# 1VD_1_5VD_1_8VD_3_3VD_3_3VA.net
KiCad netlist of a schematic drawn in Altium Designer
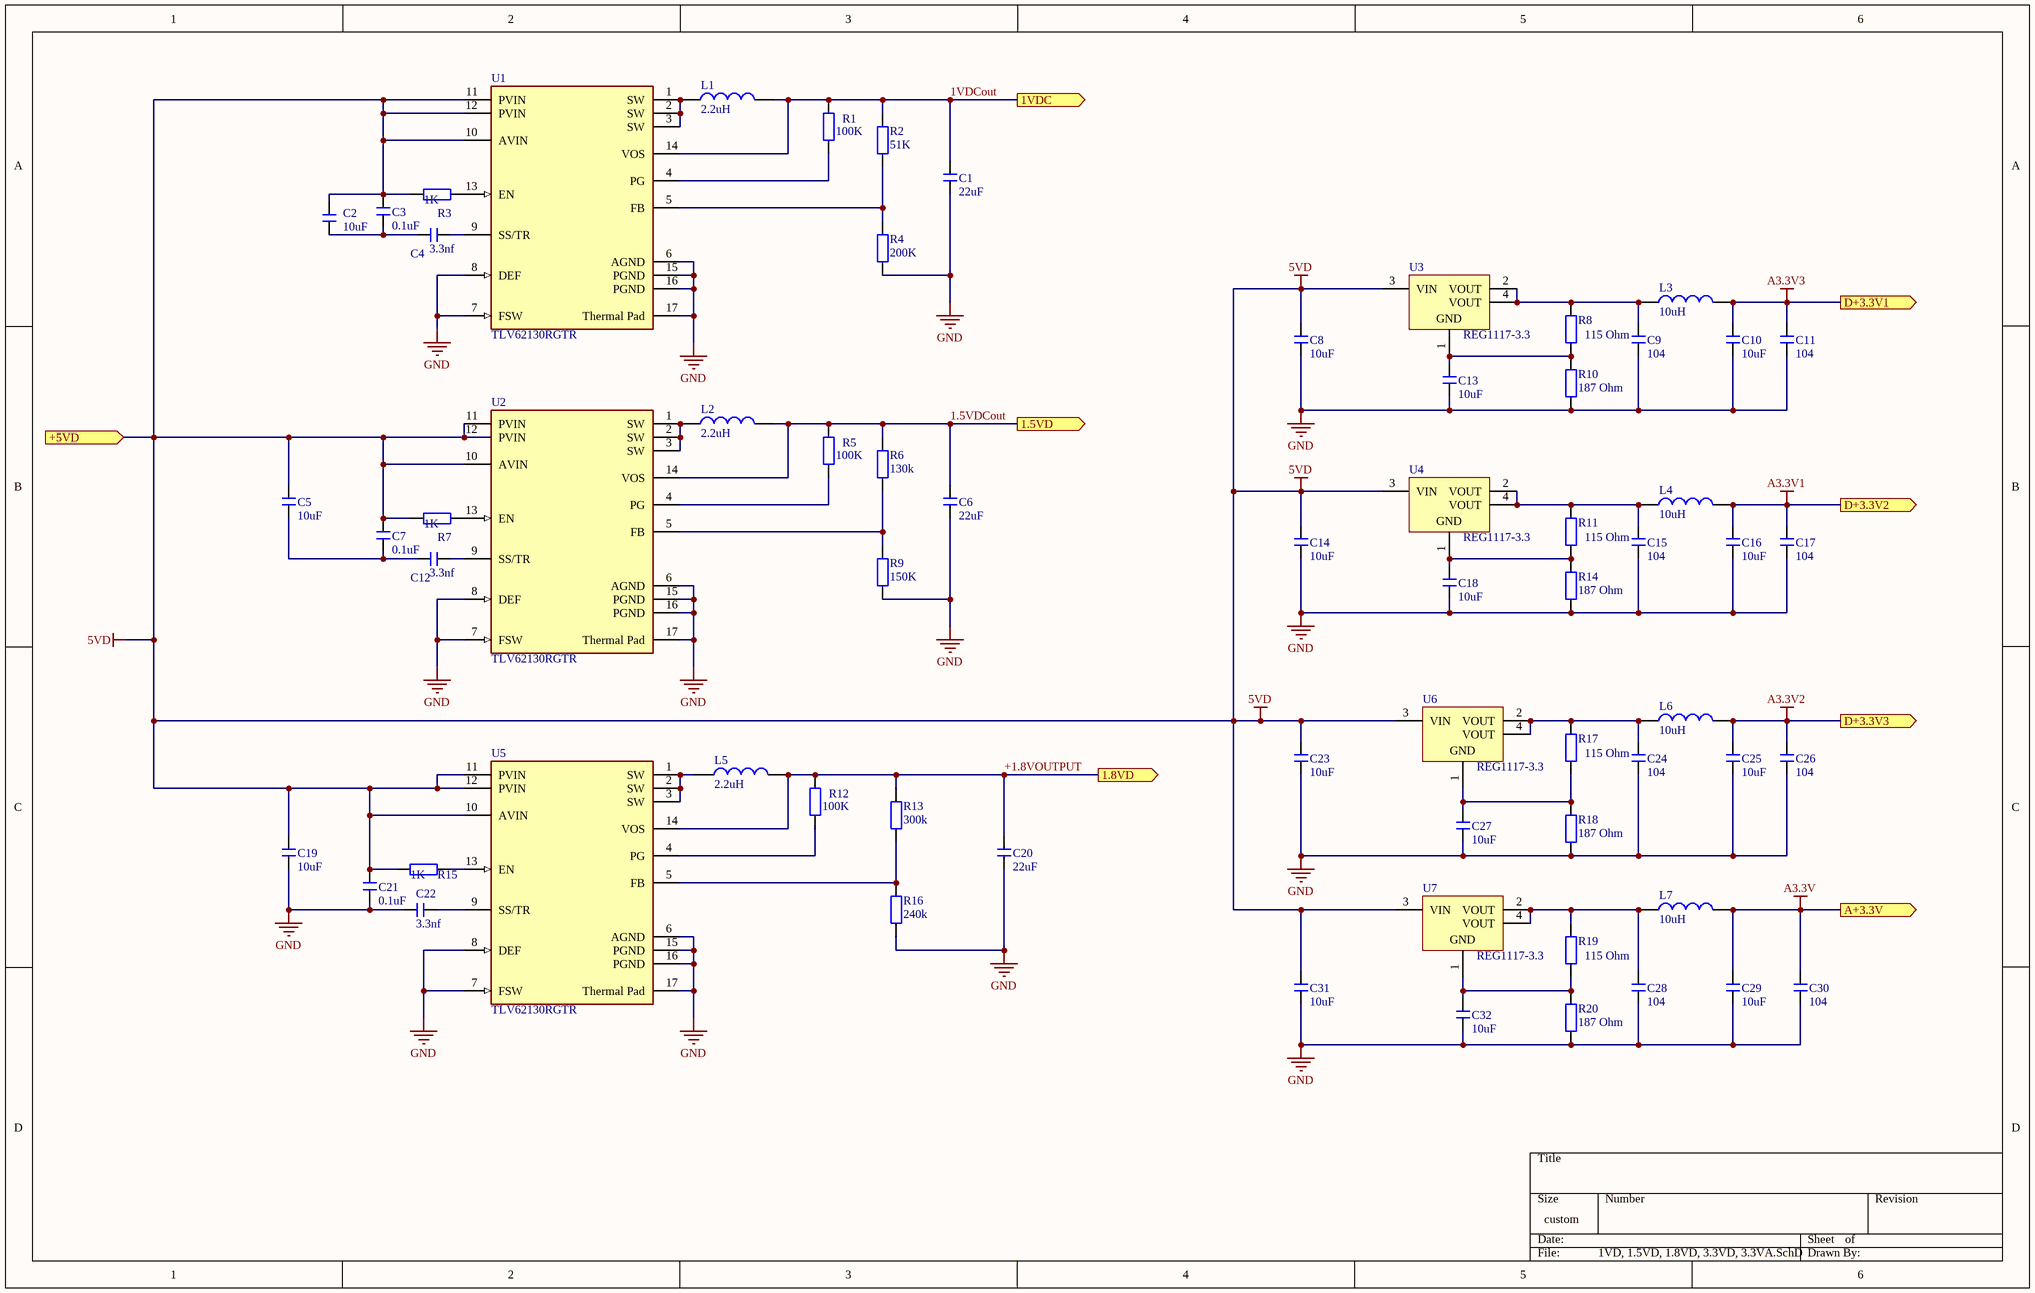
[diagram p0: 1VD, 1.5VD, 1.8VD, 3.3VD, 3.3VA.SchDoc]

(export (version "E")
  (design (tool "Eeschema 10.0.6"))
  (components
    (comp (ref "C1")
      (value "22uF")
      (footprint "C 0805_L")
      (description "贴片电容 22 µF, 6.3 V, Ceramic, 0805 Standard")
      (libsource (lib "0.1 - 电阻-电容-电感") (part "C"))
    )
    (comp (ref "C2")
      (value "10uF")
      (footprint "C 0805_L")
      (description "贴片电容 10 µF, 25 V, Ceramic, 1210 Standard")
      (libsource (lib "0.1 - 电阻-电容-电感") (part "C"))
    )
    (comp (ref "C3")
      (value "0.1uF")
      (footprint "C 0805_L")
      (description "贴片电容  \r\nC7 0.1 µF, 25V, Ceramic, 0603")
      (libsource (lib "0.1 - 电阻-电容-电感") (part "C"))
    )
    (comp (ref "C4")
      (value "3.3nf")
      (footprint "C 0805_L")
      (description "贴片电容 3300 pF, 25 V, Ceramic, 0603")
      (libsource (lib "0.1 - 电阻-电容-电感") (part "C"))
    )
    (comp (ref "C5")
      (value "10uF")
      (footprint "C 0805_L")
      (description "贴片电容 10 µF, 25 V, Ceramic, 1210 Standard")
      (libsource (lib "0.1 - 电阻-电容-电感") (part "C"))
    )
    (comp (ref "C6")
      (value "22uF")
      (footprint "C 0805_L")
      (description "贴片电容 22 µF, 6.3 V, Ceramic, 0805 Standard")
      (libsource (lib "0.1 - 电阻-电容-电感") (part "C"))
    )
    (comp (ref "C7")
      (value "0.1uF")
      (footprint "C 0805_L")
      (description "贴片电容 0.1 µF, 25V, Ceramic, 0603")
      (libsource (lib "0.1 - 电阻-电容-电感") (part "C"))
    )
    (comp (ref "C8")
      (value "10uF")
      (footprint "C 0805_L")
      (description "贴片电容")
      (libsource (lib "0.1 - 电阻-电容-电感") (part "C"))
    )
    (comp (ref "C9")
      (value "104")
      (footprint "C 0805_L")
      (description "贴片电容")
      (libsource (lib "0.1 - 电阻-电容-电感") (part "C"))
    )
    (comp (ref "C10")
      (value "10uF")
      (footprint "C 0805_L")
      (description "贴片电容")
      (libsource (lib "0.1 - 电阻-电容-电感") (part "C"))
    )
    (comp (ref "C11")
      (value "104")
      (footprint "C 0805_L")
      (description "贴片电容")
      (libsource (lib "0.1 - 电阻-电容-电感") (part "C"))
    )
    (comp (ref "C12")
      (value "3.3nf")
      (footprint "C 0805_L")
      (description "贴片电容 3300 pF, 25 V, Ceramic, 0603")
      (libsource (lib "0.1 - 电阻-电容-电感") (part "C"))
    )
    (comp (ref "C13")
      (value "10uF")
      (footprint "C 0805_L")
      (description "贴片电容")
      (libsource (lib "0.1 - 电阻-电容-电感") (part "C"))
    )
    (comp (ref "C14")
      (value "10uF")
      (footprint "C 0805_L")
      (description "贴片电容")
      (libsource (lib "0.1 - 电阻-电容-电感") (part "C"))
    )
    (comp (ref "C15")
      (value "104")
      (footprint "C 0805_L")
      (description "贴片电容")
      (libsource (lib "0.1 - 电阻-电容-电感") (part "C"))
    )
    (comp (ref "C16")
      (value "10uF")
      (footprint "C 0805_L")
      (description "贴片电容")
      (libsource (lib "0.1 - 电阻-电容-电感") (part "C"))
    )
    (comp (ref "C17")
      (value "104")
      (footprint "C 0805_L")
      (description "贴片电容")
      (libsource (lib "0.1 - 电阻-电容-电感") (part "C"))
    )
    (comp (ref "C18")
      (value "10uF")
      (footprint "C 0805_L")
      (description "贴片电容")
      (libsource (lib "0.1 - 电阻-电容-电感") (part "C"))
    )
    (comp (ref "C19")
      (value "10uF")
      (footprint "C 0805_L")
      (description "贴片电容 10 µF, 25 V, Ceramic, 1210")
      (libsource (lib "0.1 - 电阻-电容-电感") (part "C"))
    )
    (comp (ref "C20")
      (value "22uF")
      (footprint "C 0805_L")
      (description "贴片电容 22 µF, 6.3 V, Ceramic, 0805")
      (libsource (lib "0.1 - 电阻-电容-电感") (part "C"))
    )
    (comp (ref "C21")
      (value "0.1uF")
      (footprint "C 0805_L")
      (description "贴片电容")
      (libsource (lib "0.1 - 电阻-电容-电感") (part "C"))
    )
    (comp (ref "C22")
      (value "3.3nf")
      (footprint "C 0805_L")
      (description "贴片电容 3300 pF, 25 V, Ceramic, 0603")
      (libsource (lib "0.1 - 电阻-电容-电感") (part "C"))
    )
    (comp (ref "C23")
      (value "10uF")
      (footprint "C 0805_L")
      (description "贴片电容")
      (libsource (lib "0.1 - 电阻-电容-电感") (part "C"))
    )
    (comp (ref "C24")
      (value "104")
      (footprint "C 0805_L")
      (description "贴片电容")
      (libsource (lib "0.1 - 电阻-电容-电感") (part "C"))
    )
    (comp (ref "C25")
      (value "10uF")
      (footprint "C 0805_L")
      (description "贴片电容")
      (libsource (lib "0.1 - 电阻-电容-电感") (part "C"))
    )
    (comp (ref "C26")
      (value "104")
      (footprint "C 0805_L")
      (description "贴片电容")
      (libsource (lib "0.1 - 电阻-电容-电感") (part "C"))
    )
    (comp (ref "C27")
      (value "10uF")
      (footprint "C 0805_L")
      (description "贴片电容")
      (libsource (lib "0.1 - 电阻-电容-电感") (part "C"))
    )
    (comp (ref "C28")
      (value "104")
      (footprint "C 0805_L")
      (description "贴片电容")
      (libsource (lib "0.1 - 电阻-电容-电感") (part "C"))
    )
    (comp (ref "C29")
      (value "10uF")
      (footprint "C 0805_L")
      (description "贴片电容")
      (libsource (lib "0.1 - 电阻-电容-电感") (part "C"))
    )
    (comp (ref "C30")
      (value "104")
      (footprint "C 0805_L")
      (description "贴片电容")
      (libsource (lib "0.1 - 电阻-电容-电感") (part "C"))
    )
    (comp (ref "C31")
      (value "10uF")
      (footprint "C 0805_L")
      (description "贴片电容")
      (libsource (lib "0.1 - 电阻-电容-电感") (part "C"))
    )
    (comp (ref "C32")
      (value "10uF")
      (footprint "C 0805_L")
      (description "贴片电容")
      (libsource (lib "0.1 - 电阻-电容-电感") (part "C"))
    )
    (comp (ref "L1")
      (value "2.2uH")
      (footprint "L 0805")
      (description "小功率贴片电感 2.2 µH, 0.165 × 0.165 in XFL4020-222MEB, Coilcraft")
      (libsource (lib "0.1 - 电阻-电容-电感") (part "L"))
    )
    (comp (ref "L2")
      (value "2.2uH")
      (footprint "L 0805")
      (description "小功率贴片电感 2.2 µH, 0.165 × 0.165 in XFL4020-222MEB, Coilcraft")
      (libsource (lib "0.1 - 电阻-电容-电感") (part "L"))
    )
    (comp (ref "L3")
      (value "10uH")
      (footprint "AL0307")
      (description "色环电感")
      (libsource (lib "0.1 - 电阻-电容-电感") (part "L-AL"))
    )
    (comp (ref "L4")
      (value "10uH")
      (footprint "AL0307")
      (description "色环电感")
      (libsource (lib "0.1 - 电阻-电容-电感") (part "L-AL"))
    )
    (comp (ref "L5")
      (value "2.2uH")
      (footprint "L 0805")
      (description "小功率贴片电感")
      (libsource (lib "0.1 - 电阻-电容-电感") (part "L"))
    )
    (comp (ref "L6")
      (value "10uH")
      (footprint "AL0307")
      (description "色环电感")
      (libsource (lib "0.1 - 电阻-电容-电感") (part "L-AL"))
    )
    (comp (ref "L7")
      (value "10uH")
      (footprint "AL0307")
      (description "色环电感")
      (libsource (lib "0.1 - 电阻-电容-电感") (part "L-AL"))
    )
    (comp (ref "R1")
      (value "100K")
      (footprint "R 0805_L")
      (description "贴片电阻 100 kΩ, Chip, 0603, 1/16W, 1%")
      (fields (field (name "版权归属") "来自淘宝 ID：黄晶宝石"))
      (libsource (lib "0.1 - 电阻-电容-电感") (part "R"))
    )
    (comp (ref "R2")
      (value "51K")
      (footprint "R 0805_L")
      (description "贴片电阻")
      (fields (field (name "版权归属") "来自淘宝 ID：黄晶宝石"))
      (libsource (lib "0.1 - 电阻-电容-电感") (part "R"))
    )
    (comp (ref "R3")
      (value "1K")
      (footprint "R 0805_L")
      (description "贴片电阻R1 IMPORTANT, TO PREVENT HV DAMAGE")
      (fields (field (name "版权归属") "来自淘宝 ID：黄晶宝石"))
      (libsource (lib "0.1 - 电阻-电容-电感") (part "R"))
    )
    (comp (ref "R4")
      (value "200K")
      (footprint "R 0805_L")
      (description "贴片电阻")
      (fields (field (name "版权归属") "来自淘宝 ID：黄晶宝石"))
      (libsource (lib "0.1 - 电阻-电容-电感") (part "R"))
    )
    (comp (ref "R5")
      (value "100K")
      (footprint "R 0805_L")
      (description "贴片电阻 100 kΩ, Chip, 0603, 1/16W, 1%")
      (fields (field (name "版权归属") "来自淘宝 ID：黄晶宝石"))
      (libsource (lib "0.1 - 电阻-电容-电感") (part "R"))
    )
    (comp (ref "R6")
      (value "130k")
      (footprint "R 0805_L")
      (description "贴片电阻")
      (fields (field (name "版权归属") "来自淘宝 ID：黄晶宝石"))
      (libsource (lib "0.1 - 电阻-电容-电感") (part "R"))
    )
    (comp (ref "R7")
      (value "1K")
      (footprint "R 0805_L")
      (description "贴片电阻R1 IMPORTANT, TO PREVENT HV DAMAGE")
      (fields (field (name "版权归属") "来自淘宝 ID：黄晶宝石"))
      (libsource (lib "0.1 - 电阻-电容-电感") (part "R"))
    )
    (comp (ref "R8")
      (value "115 Ohm")
      (footprint "R 0805_L")
      (description "贴片电阻")
      (fields (field (name "版权归属") "来自淘宝 ID：黄晶宝石"))
      (libsource (lib "0.1 - 电阻-电容-电感") (part "R"))
    )
    (comp (ref "R9")
      (value "150K")
      (footprint "R 0805_L")
      (description "贴片电阻")
      (fields (field (name "版权归属") "来自淘宝 ID：黄晶宝石"))
      (libsource (lib "0.1 - 电阻-电容-电感") (part "R"))
    )
    (comp (ref "R10")
      (value "187 Ohm")
      (footprint "R 0805_L")
      (description "贴片电阻")
      (fields (field (name "版权归属") "来自淘宝 ID：黄晶宝石"))
      (libsource (lib "0.1 - 电阻-电容-电感") (part "R"))
    )
    (comp (ref "R11")
      (value "115 Ohm")
      (footprint "R 0805_L")
      (description "贴片电阻")
      (fields (field (name "版权归属") "来自淘宝 ID：黄晶宝石"))
      (libsource (lib "0.1 - 电阻-电容-电感") (part "R"))
    )
    (comp (ref "R12")
      (value "100K")
      (footprint "R 0805_L")
      (description "贴片电阻")
      (fields (field (name "版权归属") "来自淘宝 ID：黄晶宝石"))
      (libsource (lib "0.1 - 电阻-电容-电感") (part "R"))
    )
    (comp (ref "R13")
      (value "300k")
      (footprint "R 0805_L")
      (description "贴片电阻")
      (fields (field (name "版权归属") "来自淘宝 ID：黄晶宝石"))
      (libsource (lib "0.1 - 电阻-电容-电感") (part "R"))
    )
    (comp (ref "R14")
      (value "187 Ohm")
      (footprint "R 0805_L")
      (description "贴片电阻")
      (fields (field (name "版权归属") "来自淘宝 ID：黄晶宝石"))
      (libsource (lib "0.1 - 电阻-电容-电感") (part "R"))
    )
    (comp (ref "R15")
      (value "1K")
      (footprint "R 0805_L")
      (description "贴片电阻R1 IMPORTANT, TO PREVENT HV DAMAGE")
      (fields (field (name "版权归属") "来自淘宝 ID：黄晶宝石"))
      (libsource (lib "0.1 - 电阻-电容-电感") (part "R"))
    )
    (comp (ref "R16")
      (value "240k")
      (footprint "R 0805_L")
      (description "贴片电阻")
      (fields (field (name "版权归属") "来自淘宝 ID：黄晶宝石"))
      (libsource (lib "0.1 - 电阻-电容-电感") (part "R"))
    )
    (comp (ref "R17")
      (value "115 Ohm")
      (footprint "R 0805_L")
      (description "贴片电阻")
      (fields (field (name "版权归属") "来自淘宝 ID：黄晶宝石"))
      (libsource (lib "0.1 - 电阻-电容-电感") (part "R"))
    )
    (comp (ref "R18")
      (value "187 Ohm")
      (footprint "R 0805_L")
      (description "贴片电阻")
      (fields (field (name "版权归属") "来自淘宝 ID：黄晶宝石"))
      (libsource (lib "0.1 - 电阻-电容-电感") (part "R"))
    )
    (comp (ref "R19")
      (value "115 Ohm")
      (footprint "R 0805_L")
      (description "贴片电阻")
      (fields (field (name "版权归属") "来自淘宝 ID：黄晶宝石"))
      (libsource (lib "0.1 - 电阻-电容-电感") (part "R"))
    )
    (comp (ref "R20")
      (value "187 Ohm")
      (footprint "R 0805_L")
      (description "贴片电阻")
      (fields (field (name "版权归属") "来自淘宝 ID：黄晶宝石"))
      (libsource (lib "0.1 - 电阻-电容-电感") (part "R"))
    )
    (comp (ref "U1")
      (value "TLV62130RGTR")
      (footprint "FP-RGT0016C-IPC_A")
      (description "IC REG BUCK ADJUSTABLE 3A 16QFN")
      (fields
        (field (name "MANUFACTURER") "Texas Instruments")
        (field (name "OCTOPART") "https://octopart.com/tlv62130rgtr-texas+instruments-21766117")
      )
      (libsource (lib "Components - 23.10.23 - 12.36") (part "CMP-04918-000039-1"))
    )
    (comp (ref "U2")
      (value "TLV62130RGTR")
      (footprint "FP-RGT0016C-IPC_A")
      (description "IC REG BUCK ADJUSTABLE 3A 16QFN")
      (fields
        (field (name "MANUFACTURER") "Texas Instruments")
        (field (name "OCTOPART") "https://octopart.com/tlv62130rgtr-texas+instruments-21766117")
      )
      (libsource (lib "Components - 23.10.23 - 12.36") (part "CMP-04918-000039-1"))
    )
    (comp (ref "U3")
      (value "REG1117-3.3")
      (footprint "DCY0004A_M")
      (fields (field (name "MANUFACTURER") "Texas Instruments"))
      (libsource (lib "Components - 22.10.23 - 20.31") (part "CMP-0395-00549-2"))
    )
    (comp (ref "U4")
      (value "REG1117-3.3")
      (footprint "DCY0004A_M")
      (fields (field (name "MANUFACTURER") "Texas Instruments"))
      (libsource (lib "Components - 22.10.23 - 20.31") (part "CMP-0395-00549-2"))
    )
    (comp (ref "U5")
      (value "TLV62130RGTR")
      (footprint "FP-RGT0016C-IPC_A")
      (description "IC REG BUCK ADJUSTABLE 3A 16QFN")
      (fields
        (field (name "MANUFACTURER") "Texas Instruments")
        (field (name "OCTOPART") "https://octopart.com/tlv62130rgtr-texas+instruments-21766117")
      )
      (libsource (lib "Components - 23.10.23 - 12.36") (part "CMP-04918-000039-1"))
    )
    (comp (ref "U6")
      (value "REG1117-3.3")
      (footprint "DCY0004A_M")
      (fields (field (name "MANUFACTURER") "Texas Instruments"))
      (libsource (lib "Components - 22.10.23 - 20.31") (part "CMP-0395-00549-2"))
    )
    (comp (ref "U7")
      (value "REG1117-3.3")
      (footprint "DCY0004A_M")
      (fields (field (name "MANUFACTURER") "Texas Instruments"))
      (libsource (lib "Components - 22.10.23 - 20.31") (part "CMP-0395-00549-2"))
    )
  )
  (nets
    (net (code "1") (name "/+1.8VOUTPUT") (class "Default")
      (node (ref "C20") (pin "2") (pinfunction "2_2") (pintype "passive"))
      (node (ref "L5") (pin "2") (pinfunction "2_2") (pintype "passive"))
      (node (ref "R12") (pin "2") (pinfunction "2_2") (pintype "passive"))
      (node (ref "R13") (pin "2") (pinfunction "2_2") (pintype "passive"))
      (node (ref "U5") (pin "14") (pinfunction "VOS_14") (pintype "passive"))
    )
    (net (code "2") (name "/1.5VDCout") (class "Default")
      (node (ref "C6") (pin "2") (pinfunction "2_2") (pintype "passive"))
      (node (ref "L2") (pin "2") (pinfunction "2_2") (pintype "passive"))
      (node (ref "R5") (pin "2") (pinfunction "2_2") (pintype "passive"))
      (node (ref "R6") (pin "2") (pinfunction "2_2") (pintype "passive"))
      (node (ref "U2") (pin "14") (pinfunction "VOS_14") (pintype "passive"))
    )
    (net (code "3") (name "/1VDCout") (class "Default")
      (node (ref "C1") (pin "2") (pinfunction "2_2") (pintype "passive"))
      (node (ref "L1") (pin "2") (pinfunction "2_2") (pintype "passive"))
      (node (ref "R1") (pin "2") (pinfunction "2_2") (pintype "passive"))
      (node (ref "R2") (pin "2") (pinfunction "2_2") (pintype "passive"))
      (node (ref "U1") (pin "14") (pinfunction "VOS_14") (pintype "passive"))
    )
    (net (code "4") (name "5VD") (class "Default")
      (node (ref "C14") (pin "2") (pinfunction "2_2") (pintype "passive"))
      (node (ref "C19") (pin "2") (pinfunction "2_2") (pintype "passive"))
      (node (ref "C2") (pin "2") (pinfunction "2_2") (pintype "passive"))
      (node (ref "C21") (pin "2") (pinfunction "2_2") (pintype "passive"))
      (node (ref "C23") (pin "2") (pinfunction "2_2") (pintype "passive"))
      (node (ref "C3") (pin "2") (pinfunction "2_2") (pintype "passive"))
      (node (ref "C31") (pin "2") (pinfunction "2_2") (pintype "passive"))
      (node (ref "C5") (pin "2") (pinfunction "2_2") (pintype "passive"))
      (node (ref "C7") (pin "2") (pinfunction "2_2") (pintype "passive"))
      (node (ref "C8") (pin "2") (pinfunction "2_2") (pintype "passive"))
      (node (ref "R15") (pin "1") (pinfunction "1_1") (pintype "passive"))
      (node (ref "R3") (pin "1") (pinfunction "1_1") (pintype "passive"))
      (node (ref "R7") (pin "1") (pinfunction "1_1") (pintype "passive"))
      (node (ref "U1") (pin "10") (pinfunction "AVIN_10") (pintype "passive"))
      (node (ref "U1") (pin "11") (pinfunction "PVIN_11") (pintype "passive"))
      (node (ref "U1") (pin "12") (pinfunction "PVIN_12") (pintype "passive"))
      (node (ref "U2") (pin "10") (pinfunction "AVIN_10") (pintype "passive"))
      (node (ref "U2") (pin "11") (pinfunction "PVIN_11") (pintype "passive"))
      (node (ref "U2") (pin "12") (pinfunction "PVIN_12") (pintype "passive"))
      (node (ref "U3") (pin "3") (pinfunction "VIN_3") (pintype "passive"))
      (node (ref "U4") (pin "3") (pinfunction "VIN_3") (pintype "passive"))
      (node (ref "U5") (pin "10") (pinfunction "AVIN_10") (pintype "passive"))
      (node (ref "U5") (pin "11") (pinfunction "PVIN_11") (pintype "passive"))
      (node (ref "U5") (pin "12") (pinfunction "PVIN_12") (pintype "passive"))
      (node (ref "U6") (pin "3") (pinfunction "VIN_3") (pintype "passive"))
      (node (ref "U7") (pin "3") (pinfunction "VIN_3") (pintype "passive"))
    )
    (net (code "5") (name "A3.3V") (class "Default")
      (node (ref "C29") (pin "2") (pinfunction "2_2") (pintype "passive"))
      (node (ref "C30") (pin "2") (pinfunction "2_2") (pintype "passive"))
      (node (ref "L7") (pin "2") (pinfunction "2_2") (pintype "passive"))
    )
    (net (code "6") (name "A3.3V1") (class "Default")
      (node (ref "C16") (pin "2") (pinfunction "2_2") (pintype "passive"))
      (node (ref "C17") (pin "2") (pinfunction "2_2") (pintype "passive"))
      (node (ref "L4") (pin "2") (pinfunction "2_2") (pintype "passive"))
    )
    (net (code "7") (name "A3.3V2") (class "Default")
      (node (ref "C25") (pin "2") (pinfunction "2_2") (pintype "passive"))
      (node (ref "C26") (pin "2") (pinfunction "2_2") (pintype "passive"))
      (node (ref "L6") (pin "2") (pinfunction "2_2") (pintype "passive"))
    )
    (net (code "8") (name "A3.3V3") (class "Default")
      (node (ref "C10") (pin "2") (pinfunction "2_2") (pintype "passive"))
      (node (ref "C11") (pin "2") (pinfunction "2_2") (pintype "passive"))
      (node (ref "L3") (pin "2") (pinfunction "2_2") (pintype "passive"))
    )
    (net (code "9") (name "GND") (class "Default")
      (node (ref "C1") (pin "1") (pinfunction "1_1") (pintype "passive"))
      (node (ref "C10") (pin "1") (pinfunction "1_1") (pintype "passive"))
      (node (ref "C11") (pin "1") (pinfunction "1_1") (pintype "passive"))
      (node (ref "C13") (pin "1") (pinfunction "1_1") (pintype "passive"))
      (node (ref "C14") (pin "1") (pinfunction "1_1") (pintype "passive"))
      (node (ref "C15") (pin "1") (pinfunction "1_1") (pintype "passive"))
      (node (ref "C16") (pin "1") (pinfunction "1_1") (pintype "passive"))
      (node (ref "C17") (pin "1") (pinfunction "1_1") (pintype "passive"))
      (node (ref "C18") (pin "1") (pinfunction "1_1") (pintype "passive"))
      (node (ref "C19") (pin "1") (pinfunction "1_1") (pintype "passive"))
      (node (ref "C20") (pin "1") (pinfunction "1_1") (pintype "passive"))
      (node (ref "C21") (pin "1") (pinfunction "1_1") (pintype "passive"))
      (node (ref "C22") (pin "1") (pinfunction "1_1") (pintype "passive"))
      (node (ref "C23") (pin "1") (pinfunction "1_1") (pintype "passive"))
      (node (ref "C24") (pin "1") (pinfunction "1_1") (pintype "passive"))
      (node (ref "C25") (pin "1") (pinfunction "1_1") (pintype "passive"))
      (node (ref "C26") (pin "1") (pinfunction "1_1") (pintype "passive"))
      (node (ref "C27") (pin "1") (pinfunction "1_1") (pintype "passive"))
      (node (ref "C28") (pin "1") (pinfunction "1_1") (pintype "passive"))
      (node (ref "C29") (pin "1") (pinfunction "1_1") (pintype "passive"))
      (node (ref "C30") (pin "1") (pinfunction "1_1") (pintype "passive"))
      (node (ref "C31") (pin "1") (pinfunction "1_1") (pintype "passive"))
      (node (ref "C32") (pin "1") (pinfunction "1_1") (pintype "passive"))
      (node (ref "C6") (pin "1") (pinfunction "1_1") (pintype "passive"))
      (node (ref "C8") (pin "1") (pinfunction "1_1") (pintype "passive"))
      (node (ref "C9") (pin "1") (pinfunction "1_1") (pintype "passive"))
      (node (ref "R10") (pin "1") (pinfunction "1_1") (pintype "passive"))
      (node (ref "R14") (pin "1") (pinfunction "1_1") (pintype "passive"))
      (node (ref "R16") (pin "1") (pinfunction "1_1") (pintype "passive"))
      (node (ref "R18") (pin "1") (pinfunction "1_1") (pintype "passive"))
      (node (ref "R20") (pin "1") (pinfunction "1_1") (pintype "passive"))
      (node (ref "R4") (pin "1") (pinfunction "1_1") (pintype "passive"))
      (node (ref "R9") (pin "1") (pinfunction "1_1") (pintype "passive"))
      (node (ref "U1") (pin "15") (pinfunction "PGND_15") (pintype "power_in"))
      (node (ref "U1") (pin "16") (pinfunction "PGND_16") (pintype "power_in"))
      (node (ref "U1") (pin "17") (pinfunction "Thermal_Pad_17") (pintype "power_in"))
      (node (ref "U1") (pin "6") (pinfunction "AGND_6") (pintype "power_in"))
      (node (ref "U1") (pin "7") (pinfunction "FSW_7") (pintype "input"))
      (node (ref "U1") (pin "8") (pinfunction "DEF_8") (pintype "input"))
      (node (ref "U2") (pin "15") (pinfunction "PGND_15") (pintype "power_in"))
      (node (ref "U2") (pin "16") (pinfunction "PGND_16") (pintype "power_in"))
      (node (ref "U2") (pin "17") (pinfunction "Thermal_Pad_17") (pintype "power_in"))
      (node (ref "U2") (pin "6") (pinfunction "AGND_6") (pintype "power_in"))
      (node (ref "U2") (pin "7") (pinfunction "FSW_7") (pintype "input"))
      (node (ref "U2") (pin "8") (pinfunction "DEF_8") (pintype "input"))
      (node (ref "U5") (pin "15") (pinfunction "PGND_15") (pintype "power_in"))
      (node (ref "U5") (pin "16") (pinfunction "PGND_16") (pintype "power_in"))
      (node (ref "U5") (pin "17") (pinfunction "Thermal_Pad_17") (pintype "power_in"))
      (node (ref "U5") (pin "6") (pinfunction "AGND_6") (pintype "power_in"))
      (node (ref "U5") (pin "7") (pinfunction "FSW_7") (pintype "input"))
      (node (ref "U5") (pin "8") (pinfunction "DEF_8") (pintype "input"))
    )
    (net (code "10") (name "Net-(C2-Pad1)") (class "Default")
      (node (ref "C2") (pin "1") (pinfunction "1_1") (pintype "passive"))
      (node (ref "C3") (pin "1") (pinfunction "1_1") (pintype "passive"))
      (node (ref "C4") (pin "1") (pinfunction "1_1") (pintype "passive"))
    )
    (net (code "11") (name "Net-(C9-Pad2)") (class "Default")
      (node (ref "C9") (pin "2") (pinfunction "2_2") (pintype "passive"))
      (node (ref "L3") (pin "1") (pinfunction "1_1") (pintype "passive"))
      (node (ref "R8") (pin "2") (pinfunction "2_2") (pintype "passive"))
      (node (ref "U3") (pin "2") (pinfunction "VOUT_2") (pintype "passive"))
      (node (ref "U3") (pin "4") (pinfunction "VOUT_4") (pintype "passive"))
    )
    (net (code "12") (name "Net-(C12-Pad1)") (class "Default")
      (node (ref "C12") (pin "1") (pinfunction "1_1") (pintype "passive"))
      (node (ref "C5") (pin "1") (pinfunction "1_1") (pintype "passive"))
      (node (ref "C7") (pin "1") (pinfunction "1_1") (pintype "passive"))
    )
    (net (code "13") (name "Net-(C15-Pad2)") (class "Default")
      (node (ref "C15") (pin "2") (pinfunction "2_2") (pintype "passive"))
      (node (ref "L4") (pin "1") (pinfunction "1_1") (pintype "passive"))
      (node (ref "R11") (pin "2") (pinfunction "2_2") (pintype "passive"))
      (node (ref "U4") (pin "2") (pinfunction "VOUT_2") (pintype "passive"))
      (node (ref "U4") (pin "4") (pinfunction "VOUT_4") (pintype "passive"))
    )
    (net (code "14") (name "Net-(C24-Pad2)") (class "Default")
      (node (ref "C24") (pin "2") (pinfunction "2_2") (pintype "passive"))
      (node (ref "L6") (pin "1") (pinfunction "1_1") (pintype "passive"))
      (node (ref "R17") (pin "2") (pinfunction "2_2") (pintype "passive"))
      (node (ref "U6") (pin "2") (pinfunction "VOUT_2") (pintype "passive"))
      (node (ref "U6") (pin "4") (pinfunction "VOUT_4") (pintype "passive"))
    )
    (net (code "15") (name "Net-(C28-Pad2)") (class "Default")
      (node (ref "C28") (pin "2") (pinfunction "2_2") (pintype "passive"))
      (node (ref "L7") (pin "1") (pinfunction "1_1") (pintype "passive"))
      (node (ref "R19") (pin "2") (pinfunction "2_2") (pintype "passive"))
      (node (ref "U7") (pin "2") (pinfunction "VOUT_2") (pintype "passive"))
      (node (ref "U7") (pin "4") (pinfunction "VOUT_4") (pintype "passive"))
    )
    (net (code "16") (name "Net-(L1-Pad1)") (class "Default")
      (node (ref "L1") (pin "1") (pinfunction "1_1") (pintype "passive"))
      (node (ref "U1") (pin "1") (pinfunction "SW_1") (pintype "passive"))
      (node (ref "U1") (pin "2") (pinfunction "SW_2") (pintype "passive"))
      (node (ref "U1") (pin "3") (pinfunction "SW_3") (pintype "passive"))
    )
    (net (code "17") (name "Net-(L2-Pad1)") (class "Default")
      (node (ref "L2") (pin "1") (pinfunction "1_1") (pintype "passive"))
      (node (ref "U2") (pin "1") (pinfunction "SW_1") (pintype "passive"))
      (node (ref "U2") (pin "2") (pinfunction "SW_2") (pintype "passive"))
      (node (ref "U2") (pin "3") (pinfunction "SW_3") (pintype "passive"))
    )
    (net (code "18") (name "Net-(L5-Pad1)") (class "Default")
      (node (ref "L5") (pin "1") (pinfunction "1_1") (pintype "passive"))
      (node (ref "U5") (pin "1") (pinfunction "SW_1") (pintype "passive"))
      (node (ref "U5") (pin "2") (pinfunction "SW_2") (pintype "passive"))
      (node (ref "U5") (pin "3") (pinfunction "SW_3") (pintype "passive"))
    )
    (net (code "19") (name "Net-(U1-EN)") (class "Default")
      (node (ref "R3") (pin "2") (pinfunction "2_2") (pintype "passive"))
      (node (ref "U1") (pin "13") (pinfunction "EN_13") (pintype "input"))
    )
    (net (code "20") (name "Net-(U1-FB)") (class "Default")
      (node (ref "R2") (pin "1") (pinfunction "1_1") (pintype "passive"))
      (node (ref "R4") (pin "2") (pinfunction "2_2") (pintype "passive"))
      (node (ref "U1") (pin "5") (pinfunction "FB_5") (pintype "passive"))
    )
    (net (code "21") (name "Net-(U1-PG)") (class "Default")
      (node (ref "R1") (pin "1") (pinfunction "1_1") (pintype "passive"))
      (node (ref "U1") (pin "4") (pinfunction "PG_4") (pintype "open_collector"))
    )
    (net (code "22") (name "Net-(U1-SS{slash}TR)") (class "Default")
      (node (ref "C4") (pin "2") (pinfunction "2_2") (pintype "passive"))
      (node (ref "U1") (pin "9") (pinfunction "SS/TR_9") (pintype "passive"))
    )
    (net (code "23") (name "Net-(U2-EN)") (class "Default")
      (node (ref "R7") (pin "2") (pinfunction "2_2") (pintype "passive"))
      (node (ref "U2") (pin "13") (pinfunction "EN_13") (pintype "input"))
    )
    (net (code "24") (name "Net-(U2-FB)") (class "Default")
      (node (ref "R6") (pin "1") (pinfunction "1_1") (pintype "passive"))
      (node (ref "R9") (pin "2") (pinfunction "2_2") (pintype "passive"))
      (node (ref "U2") (pin "5") (pinfunction "FB_5") (pintype "passive"))
    )
    (net (code "25") (name "Net-(U2-PG)") (class "Default")
      (node (ref "R5") (pin "1") (pinfunction "1_1") (pintype "passive"))
      (node (ref "U2") (pin "4") (pinfunction "PG_4") (pintype "open_collector"))
    )
    (net (code "26") (name "Net-(U2-SS{slash}TR)") (class "Default")
      (node (ref "C12") (pin "2") (pinfunction "2_2") (pintype "passive"))
      (node (ref "U2") (pin "9") (pinfunction "SS/TR_9") (pintype "passive"))
    )
    (net (code "27") (name "Net-(U3-GND)") (class "Default")
      (node (ref "C13") (pin "2") (pinfunction "2_2") (pintype "passive"))
      (node (ref "R10") (pin "2") (pinfunction "2_2") (pintype "passive"))
      (node (ref "R8") (pin "1") (pinfunction "1_1") (pintype "passive"))
      (node (ref "U3") (pin "1") (pinfunction "GND_1") (pintype "power_in"))
    )
    (net (code "28") (name "Net-(U4-GND)") (class "Default")
      (node (ref "C18") (pin "2") (pinfunction "2_2") (pintype "passive"))
      (node (ref "R11") (pin "1") (pinfunction "1_1") (pintype "passive"))
      (node (ref "R14") (pin "2") (pinfunction "2_2") (pintype "passive"))
      (node (ref "U4") (pin "1") (pinfunction "GND_1") (pintype "power_in"))
    )
    (net (code "29") (name "Net-(U5-EN)") (class "Default")
      (node (ref "R15") (pin "2") (pinfunction "2_2") (pintype "passive"))
      (node (ref "U5") (pin "13") (pinfunction "EN_13") (pintype "input"))
    )
    (net (code "30") (name "Net-(U5-FB)") (class "Default")
      (node (ref "R13") (pin "1") (pinfunction "1_1") (pintype "passive"))
      (node (ref "R16") (pin "2") (pinfunction "2_2") (pintype "passive"))
      (node (ref "U5") (pin "5") (pinfunction "FB_5") (pintype "passive"))
    )
    (net (code "31") (name "Net-(U5-PG)") (class "Default")
      (node (ref "R12") (pin "1") (pinfunction "1_1") (pintype "passive"))
      (node (ref "U5") (pin "4") (pinfunction "PG_4") (pintype "open_collector"))
    )
    (net (code "32") (name "Net-(U5-SS{slash}TR)") (class "Default")
      (node (ref "C22") (pin "2") (pinfunction "2_2") (pintype "passive"))
      (node (ref "U5") (pin "9") (pinfunction "SS/TR_9") (pintype "passive"))
    )
    (net (code "33") (name "Net-(U6-GND)") (class "Default")
      (node (ref "C27") (pin "2") (pinfunction "2_2") (pintype "passive"))
      (node (ref "R17") (pin "1") (pinfunction "1_1") (pintype "passive"))
      (node (ref "R18") (pin "2") (pinfunction "2_2") (pintype "passive"))
      (node (ref "U6") (pin "1") (pinfunction "GND_1") (pintype "power_in"))
    )
    (net (code "34") (name "Net-(U7-GND)") (class "Default")
      (node (ref "C32") (pin "2") (pinfunction "2_2") (pintype "passive"))
      (node (ref "R19") (pin "1") (pinfunction "1_1") (pintype "passive"))
      (node (ref "R20") (pin "2") (pinfunction "2_2") (pintype "passive"))
      (node (ref "U7") (pin "1") (pinfunction "GND_1") (pintype "power_in"))
    )
  )
)
